# Tape.net
KiCad netlist of a schematic drawn in Altium Designer
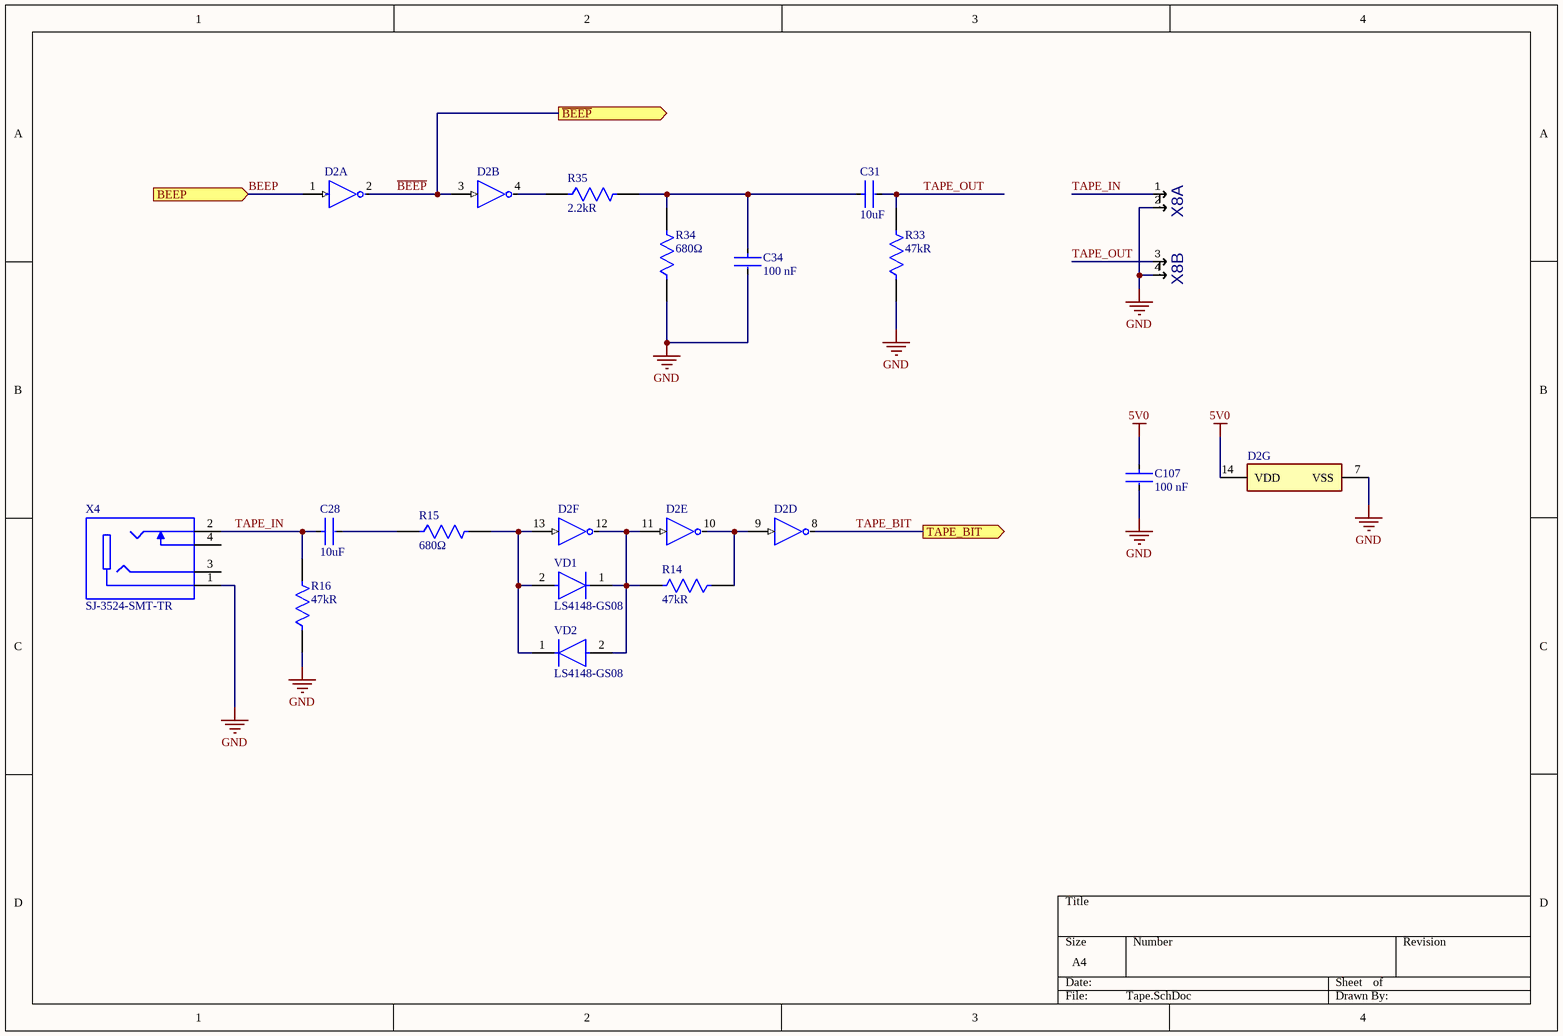
[diagram p0: Tape.SchDoc]

(export (version "E")
  (design (tool "Eeschema 10.0.6"))
  (components
    (comp (ref "C28")
      (value "C0805C106K8PACTU")
      (footprint "FP-C0805C-DG-IPC_A")
      (description "CAP CER 10UF 10V X5R 0805")
      (fields (field (name "MANUFACTURER") "KEMET") (field (name "CAPACITANCE") "10uF"))
      (libsource (lib "SchLib") (part "CMP-2007-03243-2"))
    )
    (comp (ref "C31")
      (value "C0805C106K8PACTU")
      (footprint "FP-C0805C-DG-IPC_A")
      (description "CAP CER 10UF 10V X5R 0805")
      (fields (field (name "MANUFACTURER") "KEMET") (field (name "CAPACITANCE") "10uF"))
      (libsource (lib "SchLib") (part "CMP-2007-03243-2"))
    )
    (comp (ref "C34")
      (value "CC0805KRX7R9BB104")
      (footprint "FP-CC0805-0_85-IPC_A")
      (description "CAP CER 0.1UF 50V X7R 0805")
      (fields (field (name "CAPACITANCE") "100 nF") (field (name "MANUFACTURER") "Yageo"))
      (libsource (lib "SchLib") (part "CMP-2100-03606-3"))
    )
    (comp (ref "C107")
      (value "CC0805KRX7R9BB104")
      (footprint "FP-CC0805-0_85-IPC_A")
      (description "CAP CER 0.1UF 50V X7R 0805")
      (fields (field (name "CAPACITANCE") "100 nF") (field (name "MANUFACTURER") "Yageo"))
      (libsource (lib "SchLib") (part "CMP-2100-03606-3"))
    )
    (comp (ref "D2")
      (value "CD4069UBM")
      (footprint "FP-D0014A-IPC_A")
      (description "IC INVERTER 6CH 6-INP 14SOIC")
      (fields (field (name "MANUFACTURER") "Texas Instruments"))
      (libsource (lib "SchLib") (part "CMP-1615-00195-3"))
    )
    (comp (ref "R14")
      (value "CRCW080547K0FKEAHP")
      (footprint "FP-CRCW0805-HPe3-IPC_A")
      (description "RES Thick Film, 47kΩ, 1%, 0.5W, 100ppm/°C, 0805")
      (fields (field (name "RESISTANCE") "47kR") (field (name "MANUFACTURER") "Vishay"))
      (libsource (lib "SchLib") (part "CMP-02407-008731-1"))
    )
    (comp (ref "R15")
      (value "680Ω")
      (footprint "FP-RT0805-IPC_A")
      (description "RES SMD 680 OHM 1% 1/8W 0805")
      (fields
        (field (name "MANUFACTURER") "Yageo")
        (field (name "MANUFACTURER PART NUMBER") "RT0805FRE07680RL")
      )
      (libsource (lib "SchLib") (part "CMP-03412-000082-1"))
    )
    (comp (ref "R16")
      (value "CRCW080547K0FKEAHP")
      (footprint "FP-CRCW0805-HPe3-IPC_A")
      (description "RES Thick Film, 47kΩ, 1%, 0.5W, 100ppm/°C, 0805")
      (fields (field (name "RESISTANCE") "47kR") (field (name "MANUFACTURER") "Vishay"))
      (libsource (lib "SchLib") (part "CMP-02407-008731-1"))
    )
    (comp (ref "R33")
      (value "CRCW080547K0FKEAHP")
      (footprint "FP-CRCW0805-HPe3-IPC_A")
      (description "RES Thick Film, 47kΩ, 1%, 0.5W, 100ppm/°C, 0805")
      (fields (field (name "RESISTANCE") "47kR") (field (name "MANUFACTURER") "Vishay"))
      (libsource (lib "SchLib") (part "CMP-02407-008731-1"))
    )
    (comp (ref "R34")
      (value "680Ω")
      (footprint "FP-RT0805-IPC_A")
      (description "RES SMD 680 OHM 1% 1/8W 0805")
      (fields
        (field (name "MANUFACTURER") "Yageo")
        (field (name "MANUFACTURER PART NUMBER") "RT0805FRE07680RL")
      )
      (libsource (lib "SchLib") (part "CMP-03412-000082-1"))
    )
    (comp (ref "R35")
      (value "CR0805-JW-222ELF")
      (footprint "FP-CR0805-IPC_A")
      (description "Thick Film Chip Resistors 0805 2.2kΩ 0.125W 5% 200ppm/°C")
      (fields (field (name "RESISTANCE") "2.2kR") (field (name "MANUFACTURER") "Bourns"))
      (libsource (lib "SchLib") (part "CMP-07231-003724-1"))
    )
    (comp (ref "VD1")
      (value "LS4148-GS08")
      (footprint "FP-6_560-5006_01-4-MFG")
      (description "DIODE GEN PURP 75V 150MA SOD80")
      (fields (field (name "MANUFACTURER") "Vishay"))
      (libsource (lib "SchLib") (part "CMP-02540-000025-1"))
    )
    (comp (ref "VD2")
      (value "LS4148-GS08")
      (footprint "FP-6_560-5006_01-4-MFG")
      (description "DIODE GEN PURP 75V 150MA SOD80")
      (fields (field (name "MANUFACTURER") "Vishay"))
      (libsource (lib "SchLib") (part "CMP-02540-000025-1"))
    )
    (comp (ref "X4")
      (value "SJ-3524-SMT-TR")
      (footprint "SJ-3524-SMT-TR")
      (description "Connector")
      (libsource (lib "SchLib") (part "SJ-3524-SMT-TR"))
    )
    (comp (ref "X8") (value "PLB2-2") (footprint "PLB2-2") (libsource (lib "SchLib") (part "PLB2-2")))
  )
  (nets
    (net (code "1") (name "/BEEP") (class "Default")
      (node (ref "D2") (pin "1") (pinfunction "A_1") (pintype "input"))
    )
    (net (code "2") (name "/TAPE_BIT") (class "Default")
      (node (ref "D2") (pin "8") (pinfunction "~{D}_8") (pintype "output"))
    )
    (net (code "3") (name "/TAPE_IN") (class "Default")
      (node (ref "C28") (pin "1") (pinfunction "1_1") (pintype "passive"))
      (node (ref "R16") (pin "2") (pinfunction "2_2") (pintype "passive"))
      (node (ref "X4") (pin "2") (pinfunction "2_2") (pintype "passive"))
      (node (ref "X8") (pin "1") (pinfunction "1_1") (pintype "passive"))
    )
    (net (code "4") (name "/TAPE_OUT") (class "Default")
      (node (ref "C31") (pin "2") (pinfunction "2_2") (pintype "passive"))
      (node (ref "R33") (pin "2") (pinfunction "2_2") (pintype "passive"))
      (node (ref "X8") (pin "3") (pinfunction "1_3") (pintype "passive"))
    )
    (net (code "5") (name "/~{BEEP}") (class "Default")
      (node (ref "D2") (pin "2") (pinfunction "~{A}_2") (pintype "output"))
      (node (ref "D2") (pin "3") (pinfunction "B_3") (pintype "input"))
    )
    (net (code "6") (name "5V0") (class "Default")
      (node (ref "C107") (pin "1") (pinfunction "1_1") (pintype "passive"))
      (node (ref "D2") (pin "14") (pinfunction "VDD_14") (pintype "power_in"))
    )
    (net (code "7") (name "GND") (class "Default")
      (node (ref "C107") (pin "2") (pinfunction "2_2") (pintype "passive"))
      (node (ref "C34") (pin "2") (pinfunction "2_2") (pintype "passive"))
      (node (ref "D2") (pin "7") (pinfunction "VSS_7") (pintype "power_in"))
      (node (ref "R16") (pin "1") (pinfunction "1_1") (pintype "passive"))
      (node (ref "R33") (pin "1") (pinfunction "1_1") (pintype "passive"))
      (node (ref "R34") (pin "1") (pinfunction "1_1") (pintype "passive"))
      (node (ref "X4") (pin "1") (pinfunction "1_1") (pintype "passive"))
      (node (ref "X8") (pin "2") (pinfunction "2_2") (pintype "passive"))
      (node (ref "X8") (pin "4") (pinfunction "2_4") (pintype "passive"))
    )
    (net (code "8") (name "Net-(C28-Pad2)") (class "Default")
      (node (ref "C28") (pin "2") (pinfunction "2_2") (pintype "passive"))
      (node (ref "R15") (pin "1") (pinfunction "1_1") (pintype "passive"))
    )
    (net (code "9") (name "Net-(C31-Pad1)") (class "Default")
      (node (ref "C31") (pin "1") (pinfunction "1_1") (pintype "passive"))
      (node (ref "C34") (pin "1") (pinfunction "1_1") (pintype "passive"))
      (node (ref "R34") (pin "2") (pinfunction "2_2") (pintype "passive"))
      (node (ref "R35") (pin "2") (pinfunction "2_2") (pintype "passive"))
    )
    (net (code "10") (name "Net-(D2B-~{B})") (class "Default")
      (node (ref "D2") (pin "4") (pinfunction "~{B}_4") (pintype "output"))
      (node (ref "R35") (pin "1") (pinfunction "1_1") (pintype "passive"))
    )
    (net (code "11") (name "Net-(D2D-D)") (class "Default")
      (node (ref "D2") (pin "10") (pinfunction "~{E}_10") (pintype "output"))
      (node (ref "D2") (pin "9") (pinfunction "D_9") (pintype "input"))
      (node (ref "R14") (pin "1") (pinfunction "1_1") (pintype "passive"))
    )
    (net (code "12") (name "Net-(D2E-E)") (class "Default")
      (node (ref "D2") (pin "11") (pinfunction "E_11") (pintype "input"))
      (node (ref "D2") (pin "12") (pinfunction "~{F}_12") (pintype "output"))
      (node (ref "R14") (pin "2") (pinfunction "2_2") (pintype "passive"))
      (node (ref "VD1") (pin "1") (pinfunction "C_1") (pintype "passive"))
      (node (ref "VD2") (pin "2") (pinfunction "A_2") (pintype "passive"))
    )
    (net (code "13") (name "Net-(D2F-F)") (class "Default")
      (node (ref "D2") (pin "13") (pinfunction "F_13") (pintype "input"))
      (node (ref "R15") (pin "2") (pinfunction "2_2") (pintype "passive"))
      (node (ref "VD1") (pin "2") (pinfunction "A_2") (pintype "passive"))
      (node (ref "VD2") (pin "1") (pinfunction "C_1") (pintype "passive"))
    )
    (net (code "14") (name "unconnected-(X4-Pad3)") (class "Default")
      (node (ref "X4") (pin "3") (pinfunction "3_3") (pintype "passive"))
    )
    (net (code "15") (name "unconnected-(X4-Pad4)") (class "Default")
      (node (ref "X4") (pin "4") (pinfunction "4_4") (pintype "passive"))
    )
  )
)
